# LED.net
KiCad netlist of a schematic drawn in Altium Designer
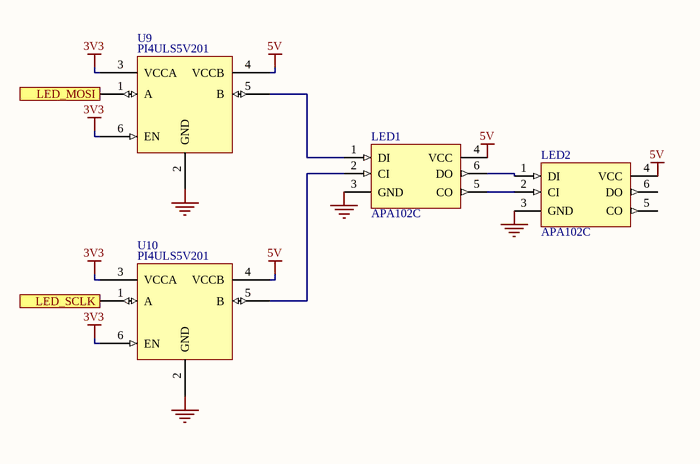
[diagram p0: LED.SchDoc]

(export (version "E")
  (design (tool "Eeschema 10.0.6"))
  (components
    (comp (ref "LED1") (value "APA102C") (footprint "5x5_WS2812") (libsource (lib "Parts") (part "APA102C")))
    (comp (ref "LED2") (value "APA102C") (footprint "5x5_WS2812") (libsource (lib "Parts") (part "APA102C")))
    (comp (ref "U9")
      (value "PI4ULS5V201")
      (footprint "SOT23-PI4ULS5V201")
      (description "Level Translator")
      (libsource (lib "Parts") (part "PI4ULS5V201"))
    )
    (comp (ref "U10")
      (value "PI4ULS5V201")
      (footprint "SOT23-PI4ULS5V201")
      (description "Level Translator")
      (libsource (lib "Parts") (part "PI4ULS5V201"))
    )
  )
  (nets
    (net (code "1") (name "/LED_MOSI") (class "Default")
      (node (ref "U9") (pin "1") (pinfunction "A_1") (pintype "bidirectional"))
    )
    (net (code "2") (name "/LED_SCLK") (class "Default")
      (node (ref "U10") (pin "1") (pinfunction "A_1") (pintype "bidirectional"))
    )
    (net (code "3") (name "3V3") (class "Default")
      (node (ref "U10") (pin "3") (pinfunction "VCCA_3") (pintype "power_in"))
      (node (ref "U10") (pin "6") (pinfunction "EN_6") (pintype "input"))
      (node (ref "U9") (pin "3") (pinfunction "VCCA_3") (pintype "power_in"))
      (node (ref "U9") (pin "6") (pinfunction "EN_6") (pintype "input"))
    )
    (net (code "4") (name "5V") (class "Default")
      (node (ref "LED1") (pin "4") (pinfunction "VCC_4") (pintype "power_in"))
      (node (ref "LED2") (pin "4") (pinfunction "VCC_4") (pintype "power_in"))
      (node (ref "U10") (pin "4") (pinfunction "VCCB_4") (pintype "power_in"))
      (node (ref "U9") (pin "4") (pinfunction "VCCB_4") (pintype "power_in"))
    )
    (net (code "5") (name "GND") (class "Default")
      (node (ref "LED1") (pin "3") (pinfunction "GND_3") (pintype "power_in"))
      (node (ref "LED2") (pin "3") (pinfunction "GND_3") (pintype "power_in"))
      (node (ref "U10") (pin "2") (pinfunction "GND_2") (pintype "power_in"))
      (node (ref "U9") (pin "2") (pinfunction "GND_2") (pintype "power_in"))
    )
    (net (code "6") (name "Net-(LED1-CI)") (class "Default")
      (node (ref "LED1") (pin "2") (pinfunction "CI_2") (pintype "input"))
      (node (ref "U10") (pin "5") (pinfunction "B_5") (pintype "bidirectional"))
    )
    (net (code "7") (name "Net-(LED1-CO)") (class "Default")
      (node (ref "LED1") (pin "5") (pinfunction "CO_5") (pintype "output"))
      (node (ref "LED2") (pin "2") (pinfunction "CI_2") (pintype "input"))
    )
    (net (code "8") (name "Net-(LED1-DI)") (class "Default")
      (node (ref "LED1") (pin "1") (pinfunction "DI_1") (pintype "input"))
      (node (ref "U9") (pin "5") (pinfunction "B_5") (pintype "bidirectional"))
    )
    (net (code "9") (name "Net-(LED1-DO)") (class "Default")
      (node (ref "LED1") (pin "6") (pinfunction "DO_6") (pintype "output"))
      (node (ref "LED2") (pin "1") (pinfunction "DI_1") (pintype "input"))
    )
    (net (code "10") (name "unconnected-(LED2-CO-Pad5)") (class "Default")
      (node (ref "LED2") (pin "5") (pinfunction "CO_5") (pintype "output"))
    )
    (net (code "11") (name "unconnected-(LED2-DO-Pad6)") (class "Default")
      (node (ref "LED2") (pin "6") (pinfunction "DO_6") (pintype "output"))
    )
  )
)
